# Power_Right.net
KiCad netlist of a schematic drawn in Altium Designer
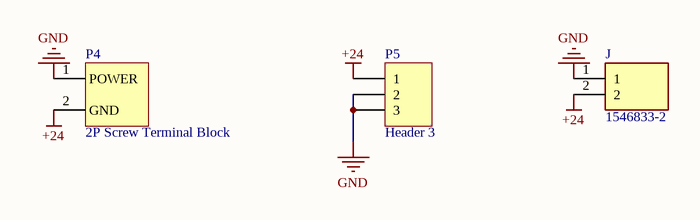
[diagram p0: Power_Right.SchDoc]

(export (version "E")
  (design (tool "Eeschema 10.0.6"))
  (components
    (comp (ref "J")
      (value "1546833-2")
      (footprint "TE_1546833-2")
      (description "2 Circuit 0.375 (9.53mm) Barrier Block Connector, Screws with Captive Plate")
      (fields (field (name "MF") "TE Connectivity"))
      (libsource (lib "1546833-2") (part "1546833-2"))
    )
    (comp (ref "P4")
      (value "2P Screw Terminal Block")
      (footprint "P_Terminal block 3.5mm-pitch")
      (description "Green Straight pin 3.5mm  pitch; P=3.5mm  Screw terminal ROHS")
      (fields (field (name "MFR PART #") "KF350-3.5-2P") (field (name "MANUFACTURER") "Cixi Kefa Elec"))
      (libsource (lib "ECEN5730Lib_2023_05_DS") (part "P_Terminal block"))
    )
    (comp (ref "P5")
      (value "Header 3")
      (footprint "HDR1X3")
      (description "Header, 3-Pin")
      (fields (field (name "PUBLISHER") "Altium Limited"))
      (libsource (lib "Miscellaneous Connectors") (part "Header 3"))
    )
  )
  (nets
    (net (code "1") (name "+24") (class "Default")
      (node (ref "J") (pin "2") (pinfunction "2_2") (pintype "passive"))
      (node (ref "P4") (pin "2") (pinfunction "GND_2") (pintype "passive"))
      (node (ref "P5") (pin "1") (pinfunction "1_1") (pintype "passive"))
    )
    (net (code "2") (name "GND") (class "Default")
      (node (ref "J") (pin "1") (pinfunction "1_1") (pintype "passive"))
      (node (ref "P4") (pin "1") (pinfunction "POWER_1") (pintype "passive"))
      (node (ref "P5") (pin "2") (pinfunction "2_2") (pintype "passive"))
      (node (ref "P5") (pin "3") (pinfunction "3_3") (pintype "passive"))
    )
  )
)
